# 13_WDT.net
KiCad netlist of a schematic drawn in Altium Designer
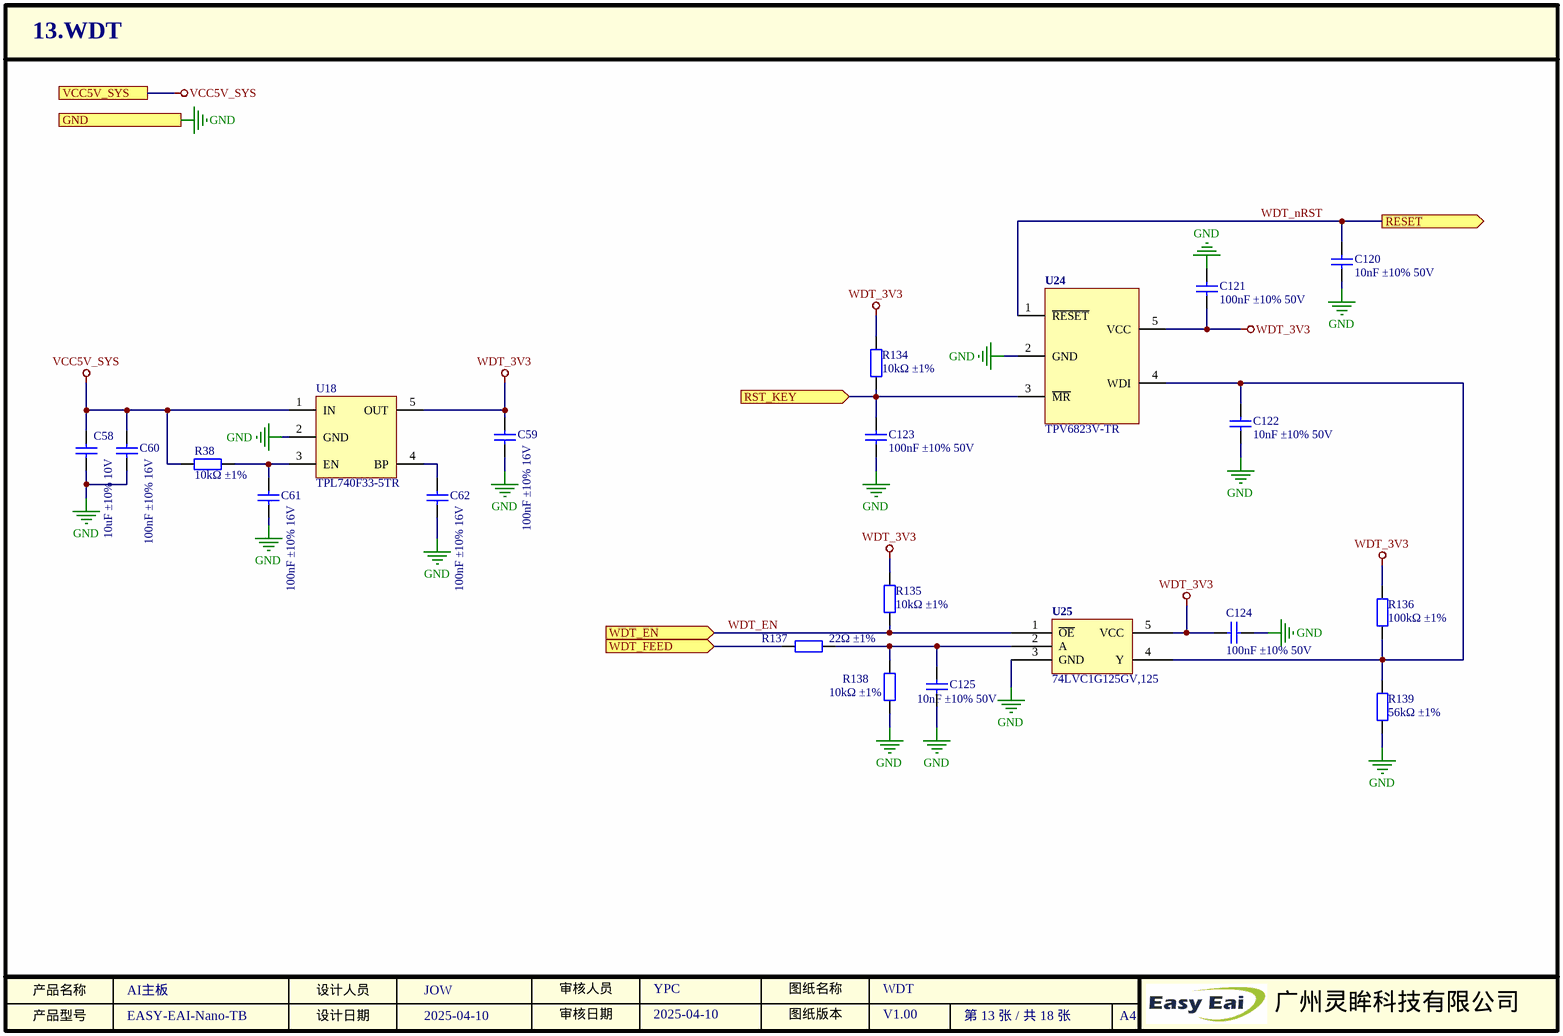
[diagram p0: 13.WDT.SchDoc]

(export (version "E")
  (design (tool "Eeschema 10.0.6"))
  (components
    (comp (ref "C58")
      (value "CL10A106KP8NNNC")
      (footprint "0603_C")
      (description "SPZL000260")
      (fields (field (name "描述") "10uF ±10% 10V"))
      (libsource (lib "CAP_lexing") (part "0603 10uF ±10% 10V"))
    )
    (comp (ref "C59")
      (value "CL05B104KO5NNNC")
      (footprint "0402_C")
      (description "SPZL000259")
      (fields (field (name "描述") "100nF ±10% 16V"))
      (libsource (lib "altium-import") (part "root_1_0402 100nF ±10% 16V_"))
    )
    (comp (ref "C60")
      (value "CL05B104KO5NNNC")
      (footprint "0402_C")
      (description "SPZL000259")
      (fields (field (name "描述") "100nF ±10% 16V"))
      (libsource (lib "altium-import") (part "root_1_0402 100nF ±10% 16V_"))
    )
    (comp (ref "C61")
      (value "CL05B104KO5NNNC")
      (footprint "0402_C")
      (description "SPZL000259")
      (fields (field (name "描述") "100nF ±10% 16V"))
      (libsource (lib "altium-import") (part "root_1_0402 100nF ±10% 16V_"))
    )
    (comp (ref "C62")
      (value "CL05B104KO5NNNC")
      (footprint "0402_C")
      (description "SPZL000259")
      (fields (field (name "描述") "100nF ±10% 16V"))
      (libsource (lib "altium-import") (part "root_1_0402 100nF ±10% 16V_"))
    )
    (comp (ref "C120")
      (value "CL05B103KB5NNNC")
      (footprint "0402_C")
      (description "SPZL000342")
      (fields (field (name "描述") "10nF ±10% 50V"))
      (libsource (lib "CAP_EASY-EAI") (part "0402 10nF ±10% 50V"))
    )
    (comp (ref "C121")
      (value "GRM155R71H104KE14D")
      (footprint "0402_C")
      (description "SPZL001162")
      (fields (field (name "描述") "100nF ±10% 50V"))
      (libsource (lib "CAP_EASY-EAI") (part "0402 100nF ±10% 50V"))
    )
    (comp (ref "C122")
      (value "CL05B103KB5NNNC")
      (footprint "0402_C")
      (description "SPZL000342")
      (fields (field (name "描述") "10nF ±10% 50V"))
      (libsource (lib "CAP_EASY-EAI") (part "0402 10nF ±10% 50V"))
    )
    (comp (ref "C123")
      (value "GRM155R71H104KE14D")
      (footprint "0402_C")
      (description "SPZL001162")
      (fields (field (name "描述") "100nF ±10% 50V"))
      (libsource (lib "CAP_EASY-EAI") (part "0402 100nF ±10% 50V"))
    )
    (comp (ref "C124")
      (value "GRM155R71H104KE14D")
      (footprint "0402_C")
      (description "SPZL001162")
      (fields (field (name "描述") "100nF ±10% 50V"))
      (libsource (lib "CAP_EASY-EAI") (part "0402 100nF ±10% 50V"))
    )
    (comp (ref "C125")
      (value "CL05B103KB5NNNC")
      (footprint "0402_C")
      (description "SPZL000342")
      (fields (field (name "描述") "10nF ±10% 50V"))
      (libsource (lib "CAP_EASY-EAI") (part "0402 10nF ±10% 50V"))
    )
    (comp (ref "R38")
      (value "0402WGF1002TCE")
      (footprint "0402_R")
      (description "SPZL000271")
      (fields (field (name "描述") "10kΩ ±1%"))
      (libsource (lib "") (part "0402 10kΩ ±1%_1"))
    )
    (comp (ref "R134")
      (value "0402WGF1002TCE")
      (footprint "0402_R")
      (description "SPZL000271")
      (fields (field (name "描述") "10kΩ ±1%"))
      (libsource (lib "RES_EASY-EAI") (part "0402 10kΩ ±1%"))
    )
    (comp (ref "R135")
      (value "0402WGF1002TCE")
      (footprint "0402_R")
      (description "SPZL000271")
      (fields (field (name "描述") "10kΩ ±1%"))
      (libsource (lib "RES_EASY-EAI") (part "0402 10kΩ ±1%"))
    )
    (comp (ref "R136")
      (value "0402WGF1003TCE")
      (footprint "0402_R")
      (description "SPZL000282")
      (fields (field (name "描述") "100kΩ ±1%"))
      (libsource (lib "RES_EASY-EAI") (part "0402 100kΩ ±1%"))
    )
    (comp (ref "R137")
      (value "0402WGF220JTCE")
      (footprint "0402_R")
      (description "SPZL000279")
      (fields (field (name "描述") "22Ω ±1%"))
      (libsource (lib "EASY-EAI-Nano-TB V1.01") (part "0402 22Ω ±1%"))
    )
    (comp (ref "R138")
      (value "0402WGF1002TCE")
      (footprint "0402_R")
      (description "SPZL000271")
      (fields (field (name "描述") "10kΩ ±1%"))
      (libsource (lib "RES_EASY-EAI") (part "0402 10kΩ ±1%"))
    )
    (comp (ref "R139")
      (value "0402WGF5602TCE")
      (footprint "0402_R")
      (description "SPZL000395")
      (fields (field (name "描述") "56kΩ ±1%"))
      (libsource (lib "RES_EASY-EAI") (part "0402 56kΩ ±1%"))
    )
    (comp (ref "U18")
      (value "TPL740F33-5TR")
      (footprint "SOT-23-5")
      (description "SPZL000784")
      (fields (field (name "型号") "TPL740F33-5TR"))
      (libsource (lib "EASY-EAI-Nano-TB V1.01") (part "TPL740F33-5TR"))
    )
    (comp (ref "U24")
      (value "TPV6823V-TR")
      (footprint "SOT-23-5")
      (description "SPZL000751")
      (fields (field (name "型号") "TPV6823V-TR"))
      (libsource (lib "IC_EASY-EAI") (part "TPV6823V-TR"))
    )
    (comp (ref "U25")
      (value "74LVC1G125GV,125")
      (footprint "SOT-23-5")
      (description "SPZL000608")
      (fields (field (name "型号") "74LVC1G125GV,125"))
      (libsource (lib "altium-import") (part "root_0_74LVC1G125GV,125_"))
    )
  )
  (nets
    (net (code "1") (name "/RST_KEY") (class "Default")
      (node (ref "C123") (pin "1") (pinfunction "1_1") (pintype "passive"))
      (node (ref "R134") (pin "1") (pinfunction "1_1") (pintype "passive"))
      (node (ref "U24") (pin "3") (pinfunction "~{MR}_3") (pintype "passive"))
    )
    (net (code "2") (name "/WDT_EN") (class "Default")
      (node (ref "R135") (pin "1") (pinfunction "1_1") (pintype "passive"))
      (node (ref "U25") (pin "1") (pinfunction "~{OE}_1") (pintype "passive"))
    )
    (net (code "3") (name "/WDT_FEED") (class "Default")
      (node (ref "R137") (pin "1") (pinfunction "1_1") (pintype "passive"))
    )
    (net (code "4") (name "/WDT_nRST") (class "Default")
      (node (ref "C120") (pin "2") (pinfunction "2_2") (pintype "passive"))
      (node (ref "U24") (pin "1") (pinfunction "~{RESET}_1") (pintype "passive"))
    )
    (net (code "5") (name "GND") (class "Default")
      (node (ref "C120") (pin "1") (pinfunction "1_1") (pintype "passive"))
      (node (ref "C121") (pin "2") (pinfunction "2_2") (pintype "passive"))
      (node (ref "C122") (pin "1") (pinfunction "1_1") (pintype "passive"))
      (node (ref "C123") (pin "2") (pinfunction "2_2") (pintype "passive"))
      (node (ref "C124") (pin "1") (pinfunction "1_1") (pintype "passive"))
      (node (ref "C125") (pin "1") (pinfunction "1_1") (pintype "passive"))
      (node (ref "C58") (pin "1") (pinfunction "1_1") (pintype "passive"))
      (node (ref "C59") (pin "1") (pinfunction "1_1") (pintype "passive"))
      (node (ref "C60") (pin "1") (pinfunction "1_1") (pintype "passive"))
      (node (ref "C61") (pin "1") (pinfunction "1_1") (pintype "passive"))
      (node (ref "C62") (pin "1") (pinfunction "1_1") (pintype "passive"))
      (node (ref "R138") (pin "1") (pinfunction "1_1") (pintype "passive"))
      (node (ref "R139") (pin "1") (pinfunction "1_1") (pintype "passive"))
      (node (ref "U18") (pin "2") (pinfunction "GND_2") (pintype "passive"))
      (node (ref "U24") (pin "2") (pinfunction "GND_2") (pintype "passive"))
      (node (ref "U25") (pin "3") (pinfunction "GND_3") (pintype "power_in"))
    )
    (net (code "6") (name "Net-(U18-BP)") (class "Default")
      (node (ref "C62") (pin "2") (pinfunction "2_2") (pintype "passive"))
      (node (ref "U18") (pin "4") (pinfunction "BP_4") (pintype "passive"))
    )
    (net (code "7") (name "Net-(U18-EN)") (class "Default")
      (node (ref "C61") (pin "2") (pinfunction "2_2") (pintype "passive"))
      (node (ref "R38") (pin "2") (pinfunction "2_2") (pintype "passive"))
      (node (ref "U18") (pin "3") (pinfunction "EN_3") (pintype "passive"))
    )
    (net (code "8") (name "Net-(U24-WDI)") (class "Default")
      (node (ref "C122") (pin "2") (pinfunction "2_2") (pintype "passive"))
      (node (ref "R136") (pin "1") (pinfunction "1_1") (pintype "passive"))
      (node (ref "R139") (pin "2") (pinfunction "2_2") (pintype "passive"))
      (node (ref "U24") (pin "4") (pinfunction "WDI_4") (pintype "passive"))
      (node (ref "U25") (pin "4") (pinfunction "Y_4") (pintype "passive"))
    )
    (net (code "9") (name "Net-(U25-A)") (class "Default")
      (node (ref "C125") (pin "2") (pinfunction "2_2") (pintype "passive"))
      (node (ref "R137") (pin "2") (pinfunction "2_2") (pintype "passive"))
      (node (ref "R138") (pin "2") (pinfunction "2_2") (pintype "passive"))
      (node (ref "U25") (pin "2") (pinfunction "A_2") (pintype "passive"))
    )
    (net (code "10") (name "VCC5V_SYS") (class "Default")
      (node (ref "C58") (pin "2") (pinfunction "2_2") (pintype "passive"))
      (node (ref "C60") (pin "2") (pinfunction "2_2") (pintype "passive"))
      (node (ref "R38") (pin "1") (pinfunction "1_1") (pintype "passive"))
      (node (ref "U18") (pin "1") (pinfunction "IN_1") (pintype "passive"))
    )
    (net (code "11") (name "WDT_3V3") (class "Default")
      (node (ref "C121") (pin "1") (pinfunction "1_1") (pintype "passive"))
      (node (ref "C124") (pin "2") (pinfunction "2_2") (pintype "passive"))
      (node (ref "C59") (pin "2") (pinfunction "2_2") (pintype "passive"))
      (node (ref "R134") (pin "2") (pinfunction "2_2") (pintype "passive"))
      (node (ref "R135") (pin "2") (pinfunction "2_2") (pintype "passive"))
      (node (ref "R136") (pin "2") (pinfunction "2_2") (pintype "passive"))
      (node (ref "U18") (pin "5") (pinfunction "OUT_5") (pintype "passive"))
      (node (ref "U24") (pin "5") (pinfunction "VCC_5") (pintype "passive"))
      (node (ref "U25") (pin "5") (pinfunction "VCC_5") (pintype "passive"))
    )
  )
)
